# Sheet1.net
KiCad netlist of a schematic drawn in Altium Designer
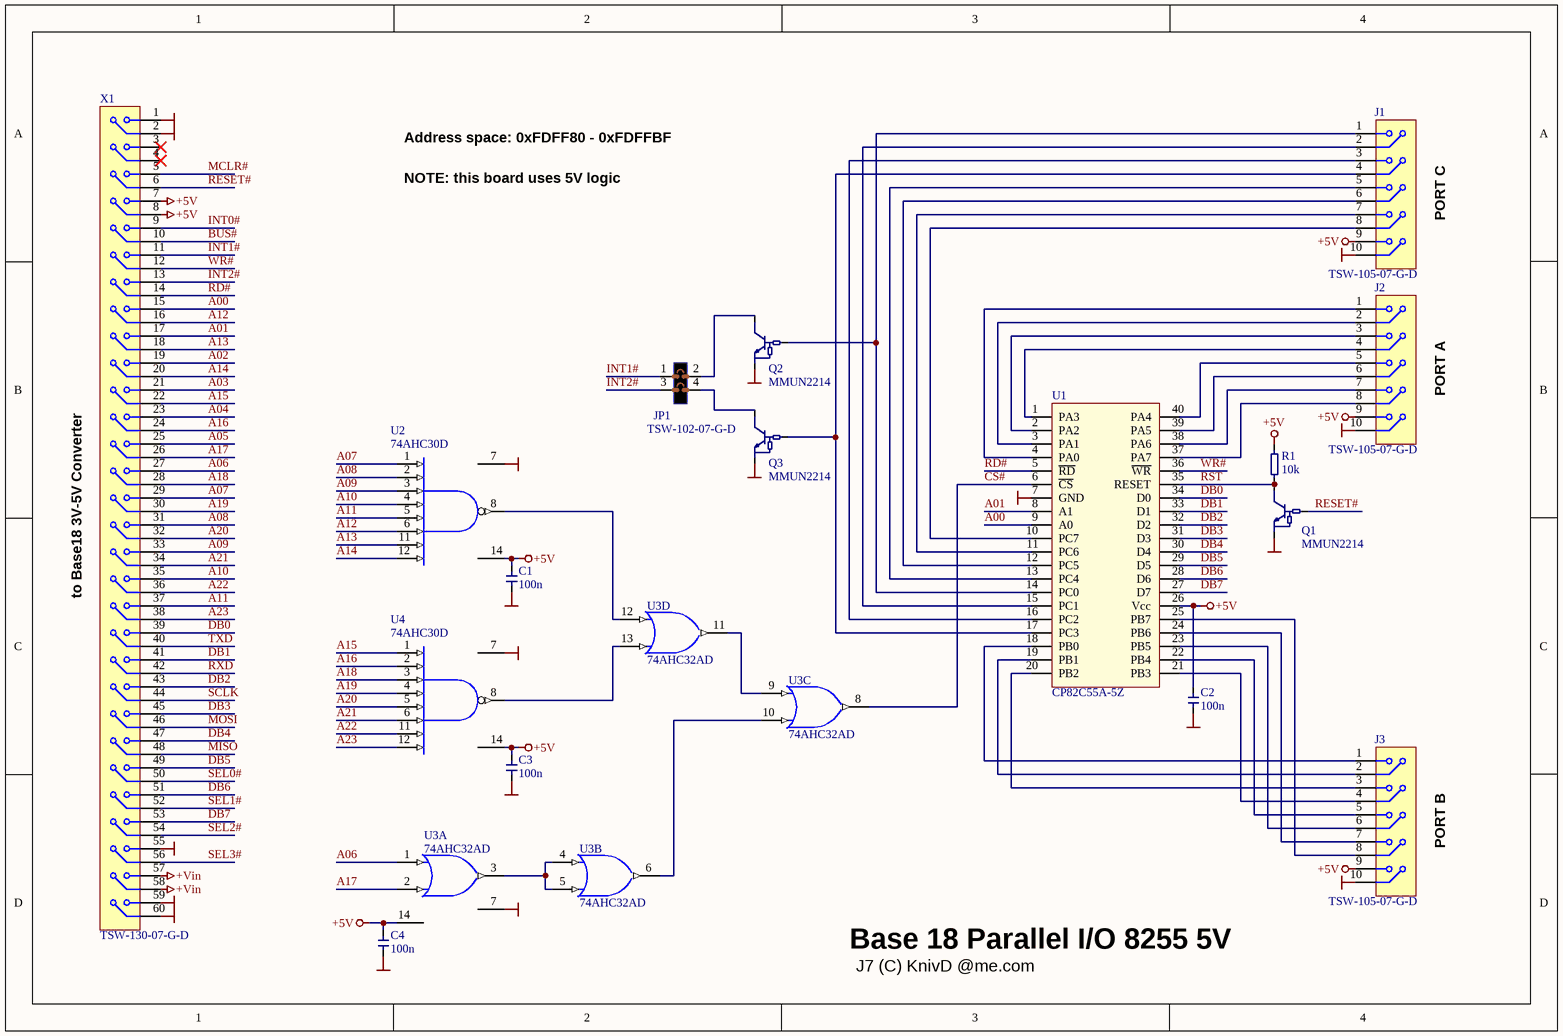
[diagram p0: Sheet1.SchDoc]

(export (version "E")
  (design (tool "Eeschema 10.0.6"))
  (components
    (comp (ref "C1")
      (value "100n")
      (footprint "CAPC3216X110N")
      (description "Capacitor")
      (libsource (lib "Discretes") (part "Capacitor"))
    )
    (comp (ref "C2")
      (value "100n")
      (footprint "CAPC3216X110N")
      (description "Capacitor")
      (libsource (lib "Discretes") (part "Capacitor"))
    )
    (comp (ref "C3")
      (value "100n")
      (footprint "CAPC3216X110N")
      (description "Capacitor")
      (libsource (lib "Discretes") (part "Capacitor"))
    )
    (comp (ref "C4")
      (value "100n")
      (footprint "CAPC3216X110N")
      (description "Capacitor")
      (libsource (lib "Discretes") (part "Capacitor"))
    )
    (comp (ref "J1")
      (value "TSW-105-07-G-D")
      (footprint "2011-2X05S")
      (description "Dual row, 10-way connector")
      (libsource (lib "Connectors") (part "Connector 2x5"))
    )
    (comp (ref "J2")
      (value "TSW-105-07-G-D")
      (footprint "2011-2X05S")
      (description "Dual row, 10-way connector")
      (libsource (lib "Connectors") (part "Connector 2x5"))
    )
    (comp (ref "J3")
      (value "TSW-105-07-G-D")
      (footprint "2011-2X05S")
      (description "Dual row, 10-way connector")
      (libsource (lib "Connectors") (part "Connector 2x5"))
    )
    (comp (ref "JP1")
      (value "TSW-102-07-G-D")
      (footprint "2011-2X02S")
      (description "2.54mm square pin header/jumper")
      (libsource (lib "Connectors") (part "Jumper 2x2"))
    )
    (comp (ref "Q1")
      (value "MMUN2214")
      (footprint "SOT23-3")
      (description "NPN biased bipolar transistor")
      (libsource (lib "Discretes") (part "NPN BIASED"))
    )
    (comp (ref "Q2")
      (value "MMUN2214")
      (footprint "SOT23-3")
      (description "NPN biased bipolar transistor")
      (libsource (lib "Discretes") (part "NPN BIASED"))
    )
    (comp (ref "Q3")
      (value "MMUN2214")
      (footprint "SOT23-3")
      (description "NPN biased bipolar transistor")
      (libsource (lib "Discretes") (part "NPN BIASED"))
    )
    (comp (ref "R1")
      (value "10k")
      (footprint "RESC3216X75N")
      (description "Resistor")
      (libsource (lib "Discretes") (part "Resistor"))
    )
    (comp (ref "U1")
      (value "CP82C55A-5Z")
      (footprint "DIP40-600")
      (description "CMOS Programmable Peripheral Interface")
      (fields (field (name "MANUFACTURER") "Renesas"))
      (libsource (lib "IC Interface") (part "82C55A DIP40"))
    )
    (comp (ref "U2")
      (value "74AHC30D")
      (footprint "SOIC14")
      (description "8-Input NAND Gate")
      (fields
        (field (name "PART NUMBER") "74HCT30N")
        (field (name "MANUFACTURER") "NXP SEMICONDUCTORS")
        (field (name "AUTHOR") "CERN DEM JLC")
      )
      (libsource (lib "ICs And Semiconductors") (part "7430"))
    )
    (comp (ref "U3")
      (value "74AHC32AD")
      (footprint "SOIC14")
      (description "Quad 2-Input OR Gate")
      (fields
        (field (name "PART NUMBER") "74HCT32N")
        (field (name "MANUFACTURER") "NXP SEMICONDUCTORS")
        (field (name "AUTHOR") "CERN DEM JLC")
      )
      (libsource (lib "ICs And Semiconductors") (part "7432"))
    )
    (comp (ref "U4")
      (value "74AHC30D")
      (footprint "SOIC14")
      (description "8-Input NAND Gate")
      (fields
        (field (name "PART NUMBER") "74HCT30N")
        (field (name "MANUFACTURER") "NXP SEMICONDUCTORS")
        (field (name "AUTHOR") "CERN DEM JLC")
      )
      (libsource (lib "ICs And Semiconductors") (part "7430"))
    )
    (comp (ref "X1")
      (value "TSW-130-07-G-D")
      (footprint "DIL60-M-EDGE")
      (description "Dual row, 60-way connector")
      (libsource (lib "Connectors") (part "Connector 2x30"))
    )
  )
  (nets
    (net (code "1") (name "+5V") (class "Default")
      (node (ref "C1") (pin "2") (pintype "passive"))
      (node (ref "C2") (pin "2") (pintype "passive"))
      (node (ref "C3") (pin "2") (pintype "passive"))
      (node (ref "C4") (pin "2") (pintype "passive"))
      (node (ref "J1") (pin "9") (pinfunction "9_9") (pintype "passive"))
      (node (ref "J2") (pin "9") (pinfunction "9_9") (pintype "passive"))
      (node (ref "J3") (pin "9") (pinfunction "9_9") (pintype "passive"))
      (node (ref "R1") (pin "1") (pintype "passive"))
      (node (ref "U1") (pin "26") (pinfunction "Vcc_26") (pintype "passive"))
      (node (ref "U2") (pin "14") (pinfunction "VCC_14") (pintype "power_in"))
      (node (ref "U3") (pin "14") (pinfunction "VCC_14") (pintype "power_in"))
      (node (ref "U4") (pin "14") (pinfunction "VCC_14") (pintype "power_in"))
      (node (ref "X1") (pin "7") (pinfunction "7_7") (pintype "passive"))
      (node (ref "X1") (pin "8") (pinfunction "8_8") (pintype "passive"))
    )
    (net (code "2") (name "+Vin") (class "Default")
      (node (ref "X1") (pin "57") (pinfunction "57_57") (pintype "passive"))
      (node (ref "X1") (pin "58") (pinfunction "58_58") (pintype "passive"))
    )
    (net (code "3") (name "/A00") (class "Default")
      (node (ref "U1") (pin "9") (pinfunction "A0_9") (pintype "passive"))
      (node (ref "X1") (pin "15") (pinfunction "15_15") (pintype "passive"))
    )
    (net (code "4") (name "/A01") (class "Default")
      (node (ref "U1") (pin "8") (pinfunction "A1_8") (pintype "passive"))
      (node (ref "X1") (pin "17") (pinfunction "17_17") (pintype "passive"))
    )
    (net (code "5") (name "/A02") (class "Default")
      (node (ref "X1") (pin "19") (pinfunction "19_19") (pintype "passive"))
    )
    (net (code "6") (name "/A03") (class "Default")
      (node (ref "X1") (pin "21") (pinfunction "21_21") (pintype "passive"))
    )
    (net (code "7") (name "/A04") (class "Default")
      (node (ref "X1") (pin "23") (pinfunction "23_23") (pintype "passive"))
    )
    (net (code "8") (name "/A05") (class "Default")
      (node (ref "X1") (pin "25") (pinfunction "25_25") (pintype "passive"))
    )
    (net (code "9") (name "/A06") (class "Default")
      (node (ref "U3") (pin "1") (pinfunction "A_1") (pintype "input"))
      (node (ref "X1") (pin "27") (pinfunction "27_27") (pintype "passive"))
    )
    (net (code "10") (name "/A07") (class "Default")
      (node (ref "U2") (pin "1") (pintype "input"))
      (node (ref "X1") (pin "29") (pinfunction "29_29") (pintype "passive"))
    )
    (net (code "11") (name "/A08") (class "Default")
      (node (ref "U2") (pin "2") (pintype "input"))
      (node (ref "X1") (pin "31") (pinfunction "31_31") (pintype "passive"))
    )
    (net (code "12") (name "/A09") (class "Default")
      (node (ref "U2") (pin "3") (pintype "input"))
      (node (ref "X1") (pin "33") (pinfunction "33_33") (pintype "passive"))
    )
    (net (code "13") (name "/A10") (class "Default")
      (node (ref "U2") (pin "4") (pintype "input"))
      (node (ref "X1") (pin "35") (pinfunction "35_35") (pintype "passive"))
    )
    (net (code "14") (name "/A11") (class "Default")
      (node (ref "U2") (pin "5") (pintype "input"))
      (node (ref "X1") (pin "37") (pinfunction "37_37") (pintype "passive"))
    )
    (net (code "15") (name "/A12") (class "Default")
      (node (ref "U2") (pin "6") (pintype "input"))
      (node (ref "X1") (pin "16") (pinfunction "16_16") (pintype "passive"))
    )
    (net (code "16") (name "/A13") (class "Default")
      (node (ref "U2") (pin "11") (pintype "input"))
      (node (ref "X1") (pin "18") (pinfunction "18_18") (pintype "passive"))
    )
    (net (code "17") (name "/A14") (class "Default")
      (node (ref "U2") (pin "12") (pintype "input"))
      (node (ref "X1") (pin "20") (pinfunction "20_20") (pintype "passive"))
    )
    (net (code "18") (name "/A15") (class "Default")
      (node (ref "U4") (pin "1") (pintype "input"))
      (node (ref "X1") (pin "22") (pinfunction "22_22") (pintype "passive"))
    )
    (net (code "19") (name "/A16") (class "Default")
      (node (ref "U4") (pin "2") (pintype "input"))
      (node (ref "X1") (pin "24") (pinfunction "24_24") (pintype "passive"))
    )
    (net (code "20") (name "/A17") (class "Default")
      (node (ref "U3") (pin "2") (pinfunction "B_2") (pintype "input"))
      (node (ref "X1") (pin "26") (pinfunction "26_26") (pintype "passive"))
    )
    (net (code "21") (name "/A18") (class "Default")
      (node (ref "U4") (pin "3") (pintype "input"))
      (node (ref "X1") (pin "28") (pinfunction "28_28") (pintype "passive"))
    )
    (net (code "22") (name "/A19") (class "Default")
      (node (ref "U4") (pin "4") (pintype "input"))
      (node (ref "X1") (pin "30") (pinfunction "30_30") (pintype "passive"))
    )
    (net (code "23") (name "/A20") (class "Default")
      (node (ref "U4") (pin "5") (pintype "input"))
      (node (ref "X1") (pin "32") (pinfunction "32_32") (pintype "passive"))
    )
    (net (code "24") (name "/A21") (class "Default")
      (node (ref "U4") (pin "6") (pintype "input"))
      (node (ref "X1") (pin "34") (pinfunction "34_34") (pintype "passive"))
    )
    (net (code "25") (name "/A22") (class "Default")
      (node (ref "U4") (pin "11") (pintype "input"))
      (node (ref "X1") (pin "36") (pinfunction "36_36") (pintype "passive"))
    )
    (net (code "26") (name "/A23") (class "Default")
      (node (ref "U4") (pin "12") (pintype "input"))
      (node (ref "X1") (pin "38") (pinfunction "38_38") (pintype "passive"))
    )
    (net (code "27") (name "/BUS#") (class "Default")
      (node (ref "X1") (pin "10") (pinfunction "10_10") (pintype "passive"))
    )
    (net (code "28") (name "/CS#") (class "Default")
      (node (ref "U1") (pin "6") (pinfunction "~{CS}_6") (pintype "passive"))
      (node (ref "U3") (pin "8") (pinfunction "Y_8") (pintype "output"))
    )
    (net (code "29") (name "/DB0") (class "Default")
      (node (ref "U1") (pin "34") (pinfunction "D0_34") (pintype "passive"))
      (node (ref "X1") (pin "39") (pinfunction "39_39") (pintype "passive"))
    )
    (net (code "30") (name "/DB1") (class "Default")
      (node (ref "U1") (pin "33") (pinfunction "D1_33") (pintype "passive"))
      (node (ref "X1") (pin "41") (pinfunction "41_41") (pintype "passive"))
    )
    (net (code "31") (name "/DB2") (class "Default")
      (node (ref "U1") (pin "32") (pinfunction "D2_32") (pintype "passive"))
      (node (ref "X1") (pin "43") (pinfunction "43_43") (pintype "passive"))
    )
    (net (code "32") (name "/DB3") (class "Default")
      (node (ref "U1") (pin "31") (pinfunction "D3_31") (pintype "passive"))
      (node (ref "X1") (pin "45") (pinfunction "45_45") (pintype "passive"))
    )
    (net (code "33") (name "/DB4") (class "Default")
      (node (ref "U1") (pin "30") (pinfunction "D4_30") (pintype "passive"))
      (node (ref "X1") (pin "47") (pinfunction "47_47") (pintype "passive"))
    )
    (net (code "34") (name "/DB5") (class "Default")
      (node (ref "U1") (pin "29") (pinfunction "D5_29") (pintype "passive"))
      (node (ref "X1") (pin "49") (pinfunction "49_49") (pintype "passive"))
    )
    (net (code "35") (name "/DB6") (class "Default")
      (node (ref "U1") (pin "28") (pinfunction "D6_28") (pintype "passive"))
      (node (ref "X1") (pin "51") (pinfunction "51_51") (pintype "passive"))
    )
    (net (code "36") (name "/DB7") (class "Default")
      (node (ref "U1") (pin "27") (pinfunction "D7_27") (pintype "passive"))
      (node (ref "X1") (pin "53") (pinfunction "53_53") (pintype "passive"))
    )
    (net (code "37") (name "/INT0#") (class "Default")
      (node (ref "X1") (pin "9") (pinfunction "9_9") (pintype "passive"))
    )
    (net (code "38") (name "/INT1#") (class "Default")
      (node (ref "JP1") (pin "1") (pintype "passive"))
      (node (ref "X1") (pin "11") (pinfunction "11_11") (pintype "passive"))
    )
    (net (code "39") (name "/INT2#") (class "Default")
      (node (ref "JP1") (pin "3") (pintype "passive"))
      (node (ref "X1") (pin "13") (pinfunction "13_13") (pintype "passive"))
    )
    (net (code "40") (name "/MCLR#") (class "Default")
      (node (ref "X1") (pin "5") (pinfunction "5_5") (pintype "passive"))
    )
    (net (code "41") (name "/MISO") (class "Default")
      (node (ref "X1") (pin "48") (pinfunction "48_48") (pintype "passive"))
    )
    (net (code "42") (name "/MOSI") (class "Default")
      (node (ref "X1") (pin "46") (pinfunction "46_46") (pintype "passive"))
    )
    (net (code "43") (name "/RD#") (class "Default")
      (node (ref "U1") (pin "5") (pinfunction "~{RD}_5") (pintype "passive"))
      (node (ref "X1") (pin "14") (pinfunction "14_14") (pintype "passive"))
    )
    (net (code "44") (name "/RESET#") (class "Default")
      (node (ref "Q1") (pin "1") (pinfunction "B_1") (pintype "passive"))
      (node (ref "X1") (pin "6") (pinfunction "6_6") (pintype "passive"))
    )
    (net (code "45") (name "/RST") (class "Default")
      (node (ref "Q1") (pin "3") (pinfunction "C_3") (pintype "passive"))
      (node (ref "R1") (pin "2") (pintype "passive"))
      (node (ref "U1") (pin "35") (pinfunction "RESET_35") (pintype "passive"))
    )
    (net (code "46") (name "/RXD") (class "Default")
      (node (ref "X1") (pin "42") (pinfunction "42_42") (pintype "passive"))
    )
    (net (code "47") (name "/SCLK") (class "Default")
      (node (ref "X1") (pin "44") (pinfunction "44_44") (pintype "passive"))
    )
    (net (code "48") (name "/SEL0#") (class "Default")
      (node (ref "X1") (pin "50") (pinfunction "50_50") (pintype "passive"))
    )
    (net (code "49") (name "/SEL1#") (class "Default")
      (node (ref "X1") (pin "52") (pinfunction "52_52") (pintype "passive"))
    )
    (net (code "50") (name "/SEL2#") (class "Default")
      (node (ref "X1") (pin "54") (pinfunction "54_54") (pintype "passive"))
    )
    (net (code "51") (name "/SEL3#") (class "Default")
      (node (ref "X1") (pin "56") (pinfunction "56_56") (pintype "passive"))
    )
    (net (code "52") (name "/TXD") (class "Default")
      (node (ref "X1") (pin "40") (pinfunction "40_40") (pintype "passive"))
    )
    (net (code "53") (name "/WR#") (class "Default")
      (node (ref "U1") (pin "36") (pinfunction "~{WR}_36") (pintype "passive"))
      (node (ref "X1") (pin "12") (pinfunction "12_12") (pintype "passive"))
    )
    (net (code "54") (name "GND") (class "Default")
      (node (ref "C1") (pin "1") (pintype "passive"))
      (node (ref "C2") (pin "1") (pintype "passive"))
      (node (ref "C3") (pin "1") (pintype "passive"))
      (node (ref "C4") (pin "1") (pintype "passive"))
      (node (ref "J1") (pin "10") (pinfunction "10_10") (pintype "passive"))
      (node (ref "J2") (pin "10") (pinfunction "10_10") (pintype "passive"))
      (node (ref "J3") (pin "10") (pinfunction "10_10") (pintype "passive"))
      (node (ref "Q1") (pin "2") (pinfunction "E_2") (pintype "passive"))
      (node (ref "Q2") (pin "2") (pinfunction "E_2") (pintype "passive"))
      (node (ref "Q3") (pin "2") (pinfunction "E_2") (pintype "passive"))
      (node (ref "U1") (pin "7") (pinfunction "GND_7") (pintype "passive"))
      (node (ref "U2") (pin "7") (pinfunction "GND_7") (pintype "power_in"))
      (node (ref "U3") (pin "7") (pinfunction "GND_7") (pintype "power_in"))
      (node (ref "U4") (pin "7") (pinfunction "GND_7") (pintype "power_in"))
      (node (ref "X1") (pin "1") (pinfunction "1_1") (pintype "passive"))
      (node (ref "X1") (pin "2") (pinfunction "2_2") (pintype "passive"))
      (node (ref "X1") (pin "55") (pinfunction "55_55") (pintype "passive"))
      (node (ref "X1") (pin "59") (pinfunction "59_59") (pintype "passive"))
      (node (ref "X1") (pin "60") (pinfunction "60_60") (pintype "passive"))
    )
    (net (code "55") (name "Net-(Q2-B)") (class "Default")
      (node (ref "J1") (pin "1") (pinfunction "1_1") (pintype "passive"))
      (node (ref "Q2") (pin "1") (pinfunction "B_1") (pintype "passive"))
      (node (ref "U1") (pin "14") (pinfunction "PC0_14") (pintype "passive"))
    )
    (net (code "56") (name "Net-(Q2-C)") (class "Default")
      (node (ref "JP1") (pin "2") (pintype "passive"))
      (node (ref "Q2") (pin "3") (pinfunction "C_3") (pintype "passive"))
    )
    (net (code "57") (name "Net-(Q3-B)") (class "Default")
      (node (ref "J1") (pin "4") (pinfunction "4_4") (pintype "passive"))
      (node (ref "Q3") (pin "1") (pinfunction "B_1") (pintype "passive"))
      (node (ref "U1") (pin "17") (pinfunction "PC3_17") (pintype "passive"))
    )
    (net (code "58") (name "Net-(Q3-C)") (class "Default")
      (node (ref "JP1") (pin "4") (pintype "passive"))
      (node (ref "Q3") (pin "3") (pinfunction "C_3") (pintype "passive"))
    )
    (net (code "59") (name "Net-(U1-PA0)") (class "Default")
      (node (ref "J2") (pin "1") (pinfunction "1_1") (pintype "passive"))
      (node (ref "U1") (pin "4") (pinfunction "PA0_4") (pintype "passive"))
    )
    (net (code "60") (name "Net-(U1-PA1)") (class "Default")
      (node (ref "J2") (pin "2") (pinfunction "2_2") (pintype "passive"))
      (node (ref "U1") (pin "3") (pinfunction "PA1_3") (pintype "passive"))
    )
    (net (code "61") (name "Net-(U1-PA2)") (class "Default")
      (node (ref "J2") (pin "3") (pinfunction "3_3") (pintype "passive"))
      (node (ref "U1") (pin "2") (pinfunction "PA2_2") (pintype "passive"))
    )
    (net (code "62") (name "Net-(U1-PA3)") (class "Default")
      (node (ref "J2") (pin "4") (pinfunction "4_4") (pintype "passive"))
      (node (ref "U1") (pin "1") (pinfunction "PA3_1") (pintype "passive"))
    )
    (net (code "63") (name "Net-(U1-PA4)") (class "Default")
      (node (ref "J2") (pin "5") (pinfunction "5_5") (pintype "passive"))
      (node (ref "U1") (pin "40") (pinfunction "PA4_40") (pintype "passive"))
    )
    (net (code "64") (name "Net-(U1-PA5)") (class "Default")
      (node (ref "J2") (pin "6") (pinfunction "6_6") (pintype "passive"))
      (node (ref "U1") (pin "39") (pinfunction "PA5_39") (pintype "passive"))
    )
    (net (code "65") (name "Net-(U1-PA6)") (class "Default")
      (node (ref "J2") (pin "7") (pinfunction "7_7") (pintype "passive"))
      (node (ref "U1") (pin "38") (pinfunction "PA6_38") (pintype "passive"))
    )
    (net (code "66") (name "Net-(U1-PA7)") (class "Default")
      (node (ref "J2") (pin "8") (pinfunction "8_8") (pintype "passive"))
      (node (ref "U1") (pin "37") (pinfunction "PA7_37") (pintype "passive"))
    )
    (net (code "67") (name "Net-(U1-PB0)") (class "Default")
      (node (ref "J3") (pin "1") (pinfunction "1_1") (pintype "passive"))
      (node (ref "U1") (pin "18") (pinfunction "PB0_18") (pintype "passive"))
    )
    (net (code "68") (name "Net-(U1-PB1)") (class "Default")
      (node (ref "J3") (pin "2") (pinfunction "2_2") (pintype "passive"))
      (node (ref "U1") (pin "19") (pinfunction "PB1_19") (pintype "passive"))
    )
    (net (code "69") (name "Net-(U1-PB2)") (class "Default")
      (node (ref "J3") (pin "3") (pinfunction "3_3") (pintype "passive"))
      (node (ref "U1") (pin "20") (pinfunction "PB2_20") (pintype "passive"))
    )
    (net (code "70") (name "Net-(U1-PB3)") (class "Default")
      (node (ref "J3") (pin "4") (pinfunction "4_4") (pintype "passive"))
      (node (ref "U1") (pin "21") (pinfunction "PB3_21") (pintype "passive"))
    )
    (net (code "71") (name "Net-(U1-PB4)") (class "Default")
      (node (ref "J3") (pin "5") (pinfunction "5_5") (pintype "passive"))
      (node (ref "U1") (pin "22") (pinfunction "PB4_22") (pintype "passive"))
    )
    (net (code "72") (name "Net-(U1-PB5)") (class "Default")
      (node (ref "J3") (pin "6") (pinfunction "6_6") (pintype "passive"))
      (node (ref "U1") (pin "23") (pinfunction "PB5_23") (pintype "passive"))
    )
    (net (code "73") (name "Net-(U1-PB6)") (class "Default")
      (node (ref "J3") (pin "7") (pinfunction "7_7") (pintype "passive"))
      (node (ref "U1") (pin "24") (pinfunction "PB6_24") (pintype "passive"))
    )
    (net (code "74") (name "Net-(U1-PB7)") (class "Default")
      (node (ref "J3") (pin "8") (pinfunction "8_8") (pintype "passive"))
      (node (ref "U1") (pin "25") (pinfunction "PB7_25") (pintype "passive"))
    )
    (net (code "75") (name "Net-(U1-PC1)") (class "Default")
      (node (ref "J1") (pin "2") (pinfunction "2_2") (pintype "passive"))
      (node (ref "U1") (pin "15") (pinfunction "PC1_15") (pintype "passive"))
    )
    (net (code "76") (name "Net-(U1-PC2)") (class "Default")
      (node (ref "J1") (pin "3") (pinfunction "3_3") (pintype "passive"))
      (node (ref "U1") (pin "16") (pinfunction "PC2_16") (pintype "passive"))
    )
    (net (code "77") (name "Net-(U1-PC4)") (class "Default")
      (node (ref "J1") (pin "5") (pinfunction "5_5") (pintype "passive"))
      (node (ref "U1") (pin "13") (pinfunction "PC4_13") (pintype "passive"))
    )
    (net (code "78") (name "Net-(U1-PC5)") (class "Default")
      (node (ref "J1") (pin "6") (pinfunction "6_6") (pintype "passive"))
      (node (ref "U1") (pin "12") (pinfunction "PC5_12") (pintype "passive"))
    )
    (net (code "79") (name "Net-(U1-PC6)") (class "Default")
      (node (ref "J1") (pin "7") (pinfunction "7_7") (pintype "passive"))
      (node (ref "U1") (pin "11") (pinfunction "PC6_11") (pintype "passive"))
    )
    (net (code "80") (name "Net-(U1-PC7)") (class "Default")
      (node (ref "J1") (pin "8") (pinfunction "8_8") (pintype "passive"))
      (node (ref "U1") (pin "10") (pinfunction "PC7_10") (pintype "passive"))
    )
    (net (code "81") (name "Net-(U3A-Y)") (class "Default")
      (node (ref "U3") (pin "3") (pinfunction "Y_3") (pintype "output"))
      (node (ref "U3") (pin "4") (pinfunction "A_4") (pintype "input"))
      (node (ref "U3") (pin "5") (pinfunction "B_5") (pintype "input"))
    )
    (net (code "82") (name "Net-(U3B-Y)") (class "Default")
      (node (ref "U3") (pin "10") (pinfunction "B_10") (pintype "input"))
      (node (ref "U3") (pin "6") (pinfunction "Y_6") (pintype "output"))
    )
    (net (code "83") (name "Net-(U3C-A)") (class "Default")
      (node (ref "U3") (pin "11") (pinfunction "Y_11") (pintype "output"))
      (node (ref "U3") (pin "9") (pinfunction "A_9") (pintype "input"))
    )
    (net (code "84") (name "Net-(U3D-A)") (class "Default")
      (node (ref "U2") (pin "8") (pintype "output"))
      (node (ref "U3") (pin "12") (pinfunction "A_12") (pintype "input"))
    )
    (net (code "85") (name "Net-(U3D-B)") (class "Default")
      (node (ref "U3") (pin "13") (pinfunction "B_13") (pintype "input"))
      (node (ref "U4") (pin "8") (pintype "output"))
    )
    (net (code "86") (name "unconnected-(X1-Pad3)") (class "Default")
      (node (ref "X1") (pin "3") (pinfunction "3_3") (pintype "passive+no_connect"))
    )
    (net (code "87") (name "unconnected-(X1-Pad4)") (class "Default")
      (node (ref "X1") (pin "4") (pinfunction "4_4") (pintype "passive+no_connect"))
    )
  )
)
